# LED_Driver.net
KiCad netlist of a schematic drawn in EAGLE
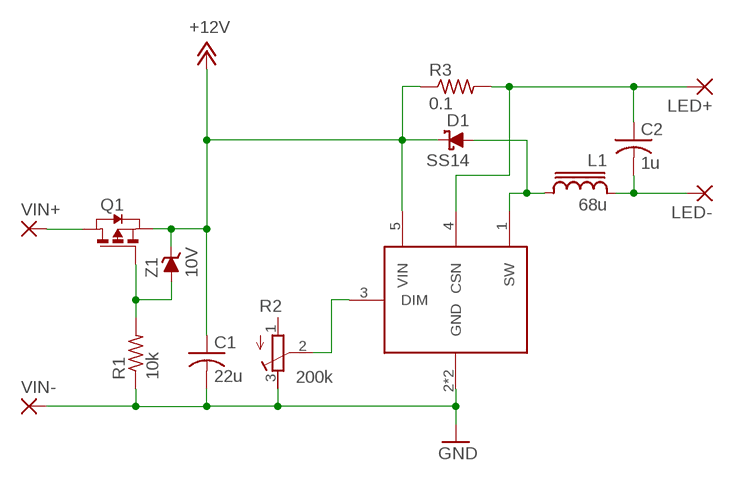
[diagram p0: schematic, sheet 1]

(export (version "E")
  (design (tool "Eeschema 10.0.6"))
  (components
    (comp (ref "C1")
      (value "22u")
      (footprint "eagle-import:C1210K")
      (libsource (lib "eagle-import") (part "C-USC1210K"))
    )
    (comp (ref "C2")
      (value "1u")
      (footprint "eagle-import:C0805K")
      (libsource (lib "eagle-import") (part "C-USC0805K"))
    )
    (comp (ref "D1")
      (value "SS14")
      (footprint "eagle-import:DO214AC")
      (libsource (lib "eagle-import") (part "SCHOTTKYSCHOTTKY-DO214AC"))
    )
    (comp (ref "IC1")
      (value "PT4115")
      (footprint "eagle-import:SOT-89-5")
      (libsource (lib "eagle-import") (part "PT4115"))
    )
    (comp (ref "L1")
      (value "68u")
      (footprint "eagle-import:CDRH127_LD")
      (libsource (lib "eagle-import") (part "CDRH127/LD"))
    )
    (comp (ref "LED+")
      (value "SMD2")
      (footprint "eagle-import:SMD1,27-2,54")
      (libsource (lib "eagle-import") (part "SMD2"))
    )
    (comp (ref "LED-")
      (value "SMD2")
      (footprint "eagle-import:SMD1,27-2,54")
      (libsource (lib "eagle-import") (part "SMD2"))
    )
    (comp (ref "Q1")
      (value "PMOSSOT23")
      (footprint "eagle-import:SOT-23")
      (libsource (lib "eagle-import") (part "PMOSSOT23"))
    )
    (comp (ref "R1")
      (value "10k")
      (footprint "eagle-import:R0805")
      (libsource (lib "eagle-import") (part "R-US_R0805"))
    )
    (comp (ref "R2")
      (value "200k")
      (footprint "eagle-import:RTRIM3296W")
      (libsource (lib "eagle-import") (part "R-TRIMM3296W"))
    )
    (comp (ref "R3")
      (value "0.1")
      (footprint "eagle-import:R2512")
      (libsource (lib "eagle-import") (part "R-US_R2512"))
    )
    (comp (ref "VIN+")
      (value "SMD2")
      (footprint "eagle-import:SMD1,27-2,54")
      (libsource (lib "eagle-import") (part "SMD2"))
    )
    (comp (ref "VIN-")
      (value "SMD2")
      (footprint "eagle-import:SMD1,27-2,54")
      (libsource (lib "eagle-import") (part "SMD2"))
    )
    (comp (ref "Z1")
      (value "10V")
      (footprint "eagle-import:SOD123")
      (libsource (lib "eagle-import") (part "ZENER"))
    )
  )
  (nets
    (net (code "1") (name "+12V") (class "Default")
      (node (ref "C1") (pin "1") (pinfunction "1_1") (pintype "passive"))
      (node (ref "D1") (pin "C") (pinfunction "C_C") (pintype "passive"))
      (node (ref "IC1") (pin "5") (pinfunction "VIN_5") (pintype "power_in"))
      (node (ref "Q1") (pin "2") (pinfunction "S_2") (pintype "passive"))
      (node (ref "R3") (pin "1") (pinfunction "1_1") (pintype "passive"))
      (node (ref "Z1") (pin "C") (pinfunction "C_C") (pintype "passive"))
    )
    (net (code "2") (name "GND") (class "Default")
      (node (ref "C1") (pin "2") (pinfunction "2_2") (pintype "passive"))
      (node (ref "IC1") (pin "2") (pinfunction "GND_2") (pintype "power_in"))
      (node (ref "IC1") (pin "EX") (pinfunction "GND_EX") (pintype "power_in"))
      (node (ref "R1") (pin "1") (pinfunction "1_1") (pintype "passive"))
      (node (ref "R2") (pin "3") (pinfunction "E_3") (pintype "passive"))
      (node (ref "VIN-") (pin "1") (pinfunction "P_1") (pintype "passive"))
    )
    (net (code "3") (name "Net-(IC1-CSN)") (class "Default")
      (node (ref "C2") (pin "1") (pinfunction "1_1") (pintype "passive"))
      (node (ref "IC1") (pin "4") (pinfunction "CSN_4") (pintype "bidirectional"))
      (node (ref "LED+") (pin "1") (pinfunction "P_1") (pintype "passive"))
      (node (ref "R3") (pin "2") (pinfunction "2_2") (pintype "passive"))
    )
    (net (code "4") (name "Net-(IC1-DIM)") (class "Default")
      (node (ref "IC1") (pin "3") (pinfunction "DIM_3") (pintype "bidirectional"))
      (node (ref "R2") (pin "2") (pinfunction "S_2") (pintype "passive"))
    )
    (net (code "5") (name "Net-(IC1-SW)") (class "Default")
      (node (ref "D1") (pin "A") (pinfunction "A_A") (pintype "passive"))
      (node (ref "IC1") (pin "1") (pinfunction "SW_1") (pintype "bidirectional"))
      (node (ref "L1") (pin "2") (pinfunction "2_2") (pintype "passive"))
    )
    (net (code "6") (name "Net-(LED--P)") (class "Default")
      (node (ref "C2") (pin "2") (pinfunction "2_2") (pintype "passive"))
      (node (ref "L1") (pin "1") (pinfunction "1_1") (pintype "passive"))
      (node (ref "LED-") (pin "1") (pinfunction "P_1") (pintype "passive"))
    )
    (net (code "7") (name "Net-(Q1-D)") (class "Default")
      (node (ref "Q1") (pin "1") (pinfunction "D_1") (pintype "passive"))
      (node (ref "VIN+") (pin "1") (pinfunction "P_1") (pintype "passive"))
    )
    (net (code "8") (name "Net-(Q1-G)") (class "Default")
      (node (ref "Q1") (pin "3") (pinfunction "G_3") (pintype "passive"))
      (node (ref "R1") (pin "2") (pinfunction "2_2") (pintype "passive"))
      (node (ref "Z1") (pin "A") (pinfunction "A_A") (pintype "passive"))
    )
    (net (code "9") (name "unconnected-(R2-A-Pad1)") (class "Default")
      (node (ref "R2") (pin "1") (pinfunction "A_1") (pintype "passive"))
    )
  )
)
